# Buffer_1_2.net
KiCad netlist of a schematic drawn in EAGLE
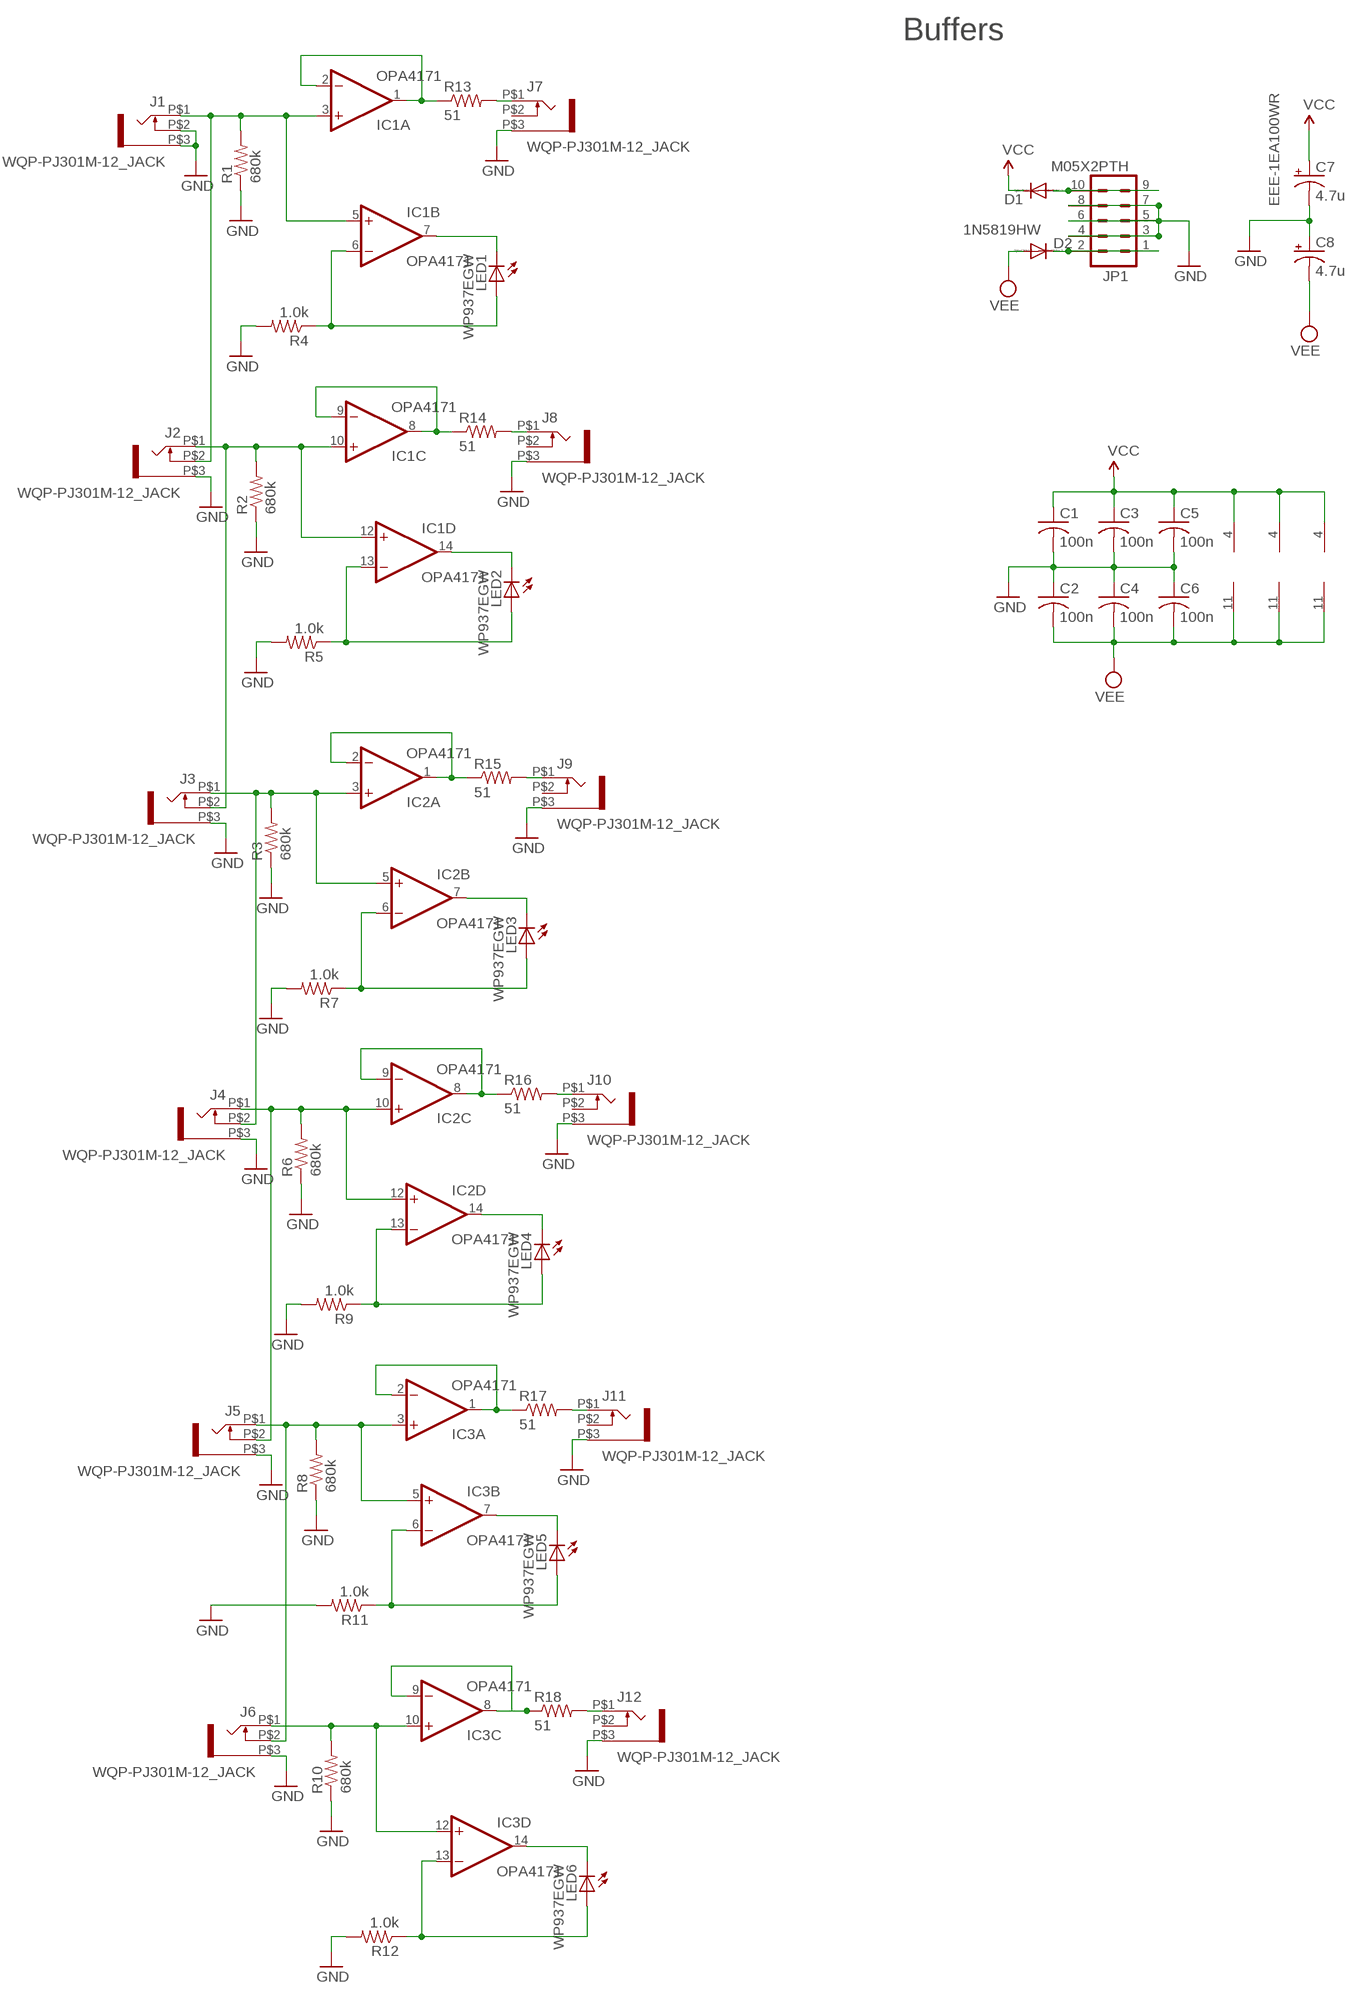
[diagram p0: schematic, sheet 1]

(export (version "E")
  (design (tool "Eeschema 10.0.6"))
  (components
    (comp (ref "C1")
      (value "100n")
      (footprint "eagle-import:C0603")
      (libsource (lib "eagle-import") (part "C-USC0603"))
    )
    (comp (ref "C2")
      (value "100n")
      (footprint "eagle-import:C0603")
      (libsource (lib "eagle-import") (part "C-USC0603"))
    )
    (comp (ref "C3")
      (value "100n")
      (footprint "eagle-import:C0603")
      (libsource (lib "eagle-import") (part "C-USC0603"))
    )
    (comp (ref "C4")
      (value "100n")
      (footprint "eagle-import:C0603")
      (libsource (lib "eagle-import") (part "C-USC0603"))
    )
    (comp (ref "C5")
      (value "100n")
      (footprint "eagle-import:C0603")
      (libsource (lib "eagle-import") (part "C-USC0603"))
    )
    (comp (ref "C6")
      (value "100n")
      (footprint "eagle-import:C0603")
      (libsource (lib "eagle-import") (part "C-USC0603"))
    )
    (comp (ref "C7")
      (value "4.7u")
      (footprint "eagle-import:PANASONIC_A")
      (libsource (lib "eagle-import") (part "CPOL-USA"))
    )
    (comp (ref "C8")
      (value "4.7u")
      (footprint "eagle-import:PANASONIC_A")
      (libsource (lib "eagle-import") (part "CPOL-USA"))
    )
    (comp (ref "D1")
      (value "1N5819HW")
      (footprint "eagle-import:SOD123")
      (libsource (lib "eagle-import") (part "DIODE-SOD123"))
    )
    (comp (ref "D2")
      (value "1N5819HW")
      (footprint "eagle-import:SOD123")
      (libsource (lib "eagle-import") (part "DIODE-SOD123"))
    )
    (comp (ref "IC1")
      (value "OPA4171")
      (footprint "eagle-import:TSSOP14")
      (libsource (lib "eagle-import") (part "TL074PW"))
    )
    (comp (ref "IC2")
      (value "OPA4171")
      (footprint "eagle-import:TSSOP14")
      (libsource (lib "eagle-import") (part "TL074PW"))
    )
    (comp (ref "IC3")
      (value "OPA4171")
      (footprint "eagle-import:TSSOP14")
      (libsource (lib "eagle-import") (part "TL074PW"))
    )
    (comp (ref "J1")
      (value "WQP-PJ301M-12_JACK")
      (footprint "eagle-import:WQP-PJ301M-12_JACK")
      (libsource (lib "eagle-import") (part "WQP-PJ301M-12_JACK"))
    )
    (comp (ref "J2")
      (value "WQP-PJ301M-12_JACK")
      (footprint "eagle-import:WQP-PJ301M-12_JACK")
      (libsource (lib "eagle-import") (part "WQP-PJ301M-12_JACK"))
    )
    (comp (ref "J3")
      (value "WQP-PJ301M-12_JACK")
      (footprint "eagle-import:WQP-PJ301M-12_JACK")
      (libsource (lib "eagle-import") (part "WQP-PJ301M-12_JACK"))
    )
    (comp (ref "J4")
      (value "WQP-PJ301M-12_JACK")
      (footprint "eagle-import:WQP-PJ301M-12_JACK")
      (libsource (lib "eagle-import") (part "WQP-PJ301M-12_JACK"))
    )
    (comp (ref "J5")
      (value "WQP-PJ301M-12_JACK")
      (footprint "eagle-import:WQP-PJ301M-12_JACK")
      (libsource (lib "eagle-import") (part "WQP-PJ301M-12_JACK"))
    )
    (comp (ref "J6")
      (value "WQP-PJ301M-12_JACK")
      (footprint "eagle-import:WQP-PJ301M-12_JACK")
      (libsource (lib "eagle-import") (part "WQP-PJ301M-12_JACK"))
    )
    (comp (ref "J7")
      (value "WQP-PJ301M-12_JACK")
      (footprint "eagle-import:WQP-PJ301M-12_JACK")
      (libsource (lib "eagle-import") (part "WQP-PJ301M-12_JACK"))
    )
    (comp (ref "J8")
      (value "WQP-PJ301M-12_JACK")
      (footprint "eagle-import:WQP-PJ301M-12_JACK")
      (libsource (lib "eagle-import") (part "WQP-PJ301M-12_JACK"))
    )
    (comp (ref "J9")
      (value "WQP-PJ301M-12_JACK")
      (footprint "eagle-import:WQP-PJ301M-12_JACK")
      (libsource (lib "eagle-import") (part "WQP-PJ301M-12_JACK"))
    )
    (comp (ref "J10")
      (value "WQP-PJ301M-12_JACK")
      (footprint "eagle-import:WQP-PJ301M-12_JACK")
      (libsource (lib "eagle-import") (part "WQP-PJ301M-12_JACK"))
    )
    (comp (ref "J11")
      (value "WQP-PJ301M-12_JACK")
      (footprint "eagle-import:WQP-PJ301M-12_JACK")
      (libsource (lib "eagle-import") (part "WQP-PJ301M-12_JACK"))
    )
    (comp (ref "J12")
      (value "WQP-PJ301M-12_JACK")
      (footprint "eagle-import:WQP-PJ301M-12_JACK")
      (libsource (lib "eagle-import") (part "WQP-PJ301M-12_JACK"))
    )
    (comp (ref "JP1")
      (value "M05X2PTH")
      (footprint "eagle-import:AVR_ICSP")
      (libsource (lib "eagle-import") (part "M05X2PTH"))
    )
    (comp (ref "LED1")
      (value "WP937EGW")
      (footprint "eagle-import:LED3MM")
      (libsource (lib "eagle-import") (part "LED3MM"))
    )
    (comp (ref "LED2")
      (value "WP937EGW")
      (footprint "eagle-import:LED3MM")
      (libsource (lib "eagle-import") (part "LED3MM"))
    )
    (comp (ref "LED3")
      (value "WP937EGW")
      (footprint "eagle-import:LED3MM")
      (libsource (lib "eagle-import") (part "LED3MM"))
    )
    (comp (ref "LED4")
      (value "WP937EGW")
      (footprint "eagle-import:LED3MM")
      (libsource (lib "eagle-import") (part "LED3MM"))
    )
    (comp (ref "LED5")
      (value "WP937EGW")
      (footprint "eagle-import:LED3MM")
      (libsource (lib "eagle-import") (part "LED3MM"))
    )
    (comp (ref "LED6")
      (value "WP937EGW")
      (footprint "eagle-import:LED3MM")
      (libsource (lib "eagle-import") (part "LED3MM"))
    )
    (comp (ref "R1")
      (value "680k")
      (footprint "eagle-import:R0603")
      (libsource (lib "eagle-import") (part "resistor_348_R-US_R0603"))
    )
    (comp (ref "R2")
      (value "680k")
      (footprint "eagle-import:R0603")
      (libsource (lib "eagle-import") (part "resistor_348_R-US_R0603"))
    )
    (comp (ref "R3")
      (value "680k")
      (footprint "eagle-import:R0603")
      (libsource (lib "eagle-import") (part "resistor_348_R-US_R0603"))
    )
    (comp (ref "R4")
      (value "1.0k")
      (footprint "eagle-import:R0603")
      (libsource (lib "eagle-import") (part "R-US_R0603"))
    )
    (comp (ref "R5")
      (value "1.0k")
      (footprint "eagle-import:R0603")
      (libsource (lib "eagle-import") (part "R-US_R0603"))
    )
    (comp (ref "R6")
      (value "680k")
      (footprint "eagle-import:R0603")
      (libsource (lib "eagle-import") (part "resistor_348_R-US_R0603"))
    )
    (comp (ref "R7")
      (value "1.0k")
      (footprint "eagle-import:R0603")
      (libsource (lib "eagle-import") (part "R-US_R0603"))
    )
    (comp (ref "R8")
      (value "680k")
      (footprint "eagle-import:R0603")
      (libsource (lib "eagle-import") (part "resistor_348_R-US_R0603"))
    )
    (comp (ref "R9")
      (value "1.0k")
      (footprint "eagle-import:R0603")
      (libsource (lib "eagle-import") (part "R-US_R0603"))
    )
    (comp (ref "R10")
      (value "680k")
      (footprint "eagle-import:R0603")
      (libsource (lib "eagle-import") (part "resistor_348_R-US_R0603"))
    )
    (comp (ref "R11")
      (value "1.0k")
      (footprint "eagle-import:R0603")
      (libsource (lib "eagle-import") (part "R-US_R0603"))
    )
    (comp (ref "R12")
      (value "1.0k")
      (footprint "eagle-import:R0603")
      (libsource (lib "eagle-import") (part "R-US_R0603"))
    )
    (comp (ref "R13")
      (value "51")
      (footprint "eagle-import:R0603")
      (libsource (lib "eagle-import") (part "resistor_348_R-US_R0603"))
    )
    (comp (ref "R14")
      (value "51")
      (footprint "eagle-import:R0603")
      (libsource (lib "eagle-import") (part "resistor_348_R-US_R0603"))
    )
    (comp (ref "R15")
      (value "51")
      (footprint "eagle-import:R0603")
      (libsource (lib "eagle-import") (part "resistor_348_R-US_R0603"))
    )
    (comp (ref "R16")
      (value "51")
      (footprint "eagle-import:R0603")
      (libsource (lib "eagle-import") (part "resistor_348_R-US_R0603"))
    )
    (comp (ref "R17")
      (value "51")
      (footprint "eagle-import:R0603")
      (libsource (lib "eagle-import") (part "resistor_348_R-US_R0603"))
    )
    (comp (ref "R18")
      (value "51")
      (footprint "eagle-import:R0603")
      (libsource (lib "eagle-import") (part "resistor_348_R-US_R0603"))
    )
  )
  (nets
    (net (code "1") (name "GND") (class "Default")
      (node (ref "C1") (pin "2") (pinfunction "2_2") (pintype "passive"))
      (node (ref "C2") (pin "1") (pinfunction "1_1") (pintype "passive"))
      (node (ref "C3") (pin "2") (pinfunction "2_2") (pintype "passive"))
      (node (ref "C4") (pin "1") (pinfunction "1_1") (pintype "passive"))
      (node (ref "C5") (pin "2") (pinfunction "2_2") (pintype "passive"))
      (node (ref "C6") (pin "1") (pinfunction "1_1") (pintype "passive"))
      (node (ref "C7") (pin "-") (pinfunction "-_-") (pintype "passive"))
      (node (ref "C8") (pin "+") (pinfunction "+_+") (pintype "passive"))
      (node (ref "J1") (pin "P$2") (pinfunction "3_P$2") (pintype "passive"))
      (node (ref "J1") (pin "P$3") (pinfunction "1_P$3") (pintype "passive"))
      (node (ref "J10") (pin "P$3") (pinfunction "1_P$3") (pintype "passive"))
      (node (ref "J11") (pin "P$3") (pinfunction "1_P$3") (pintype "passive"))
      (node (ref "J12") (pin "P$3") (pinfunction "1_P$3") (pintype "passive"))
      (node (ref "J2") (pin "P$3") (pinfunction "1_P$3") (pintype "passive"))
      (node (ref "J3") (pin "P$3") (pinfunction "1_P$3") (pintype "passive"))
      (node (ref "J4") (pin "P$3") (pinfunction "1_P$3") (pintype "passive"))
      (node (ref "J5") (pin "P$3") (pinfunction "1_P$3") (pintype "passive"))
      (node (ref "J6") (pin "P$3") (pinfunction "1_P$3") (pintype "passive"))
      (node (ref "J7") (pin "P$3") (pinfunction "1_P$3") (pintype "passive"))
      (node (ref "J8") (pin "P$3") (pinfunction "1_P$3") (pintype "passive"))
      (node (ref "J9") (pin "P$3") (pinfunction "1_P$3") (pintype "passive"))
      (node (ref "JP1") (pin "3") (pinfunction "3_3") (pintype "passive"))
      (node (ref "JP1") (pin "4") (pinfunction "4_4") (pintype "passive"))
      (node (ref "JP1") (pin "5") (pinfunction "5_5") (pintype "passive"))
      (node (ref "JP1") (pin "6") (pinfunction "6_6") (pintype "passive"))
      (node (ref "JP1") (pin "7") (pinfunction "7_7") (pintype "passive"))
      (node (ref "JP1") (pin "8") (pinfunction "8_8") (pintype "passive"))
      (node (ref "R1") (pin "1") (pinfunction "1_1") (pintype "passive"))
      (node (ref "R10") (pin "1") (pinfunction "1_1") (pintype "passive"))
      (node (ref "R11") (pin "2") (pinfunction "2_2") (pintype "passive"))
      (node (ref "R12") (pin "2") (pinfunction "2_2") (pintype "passive"))
      (node (ref "R2") (pin "1") (pinfunction "1_1") (pintype "passive"))
      (node (ref "R3") (pin "1") (pinfunction "1_1") (pintype "passive"))
      (node (ref "R4") (pin "2") (pinfunction "2_2") (pintype "passive"))
      (node (ref "R5") (pin "2") (pinfunction "2_2") (pintype "passive"))
      (node (ref "R6") (pin "1") (pinfunction "1_1") (pintype "passive"))
      (node (ref "R7") (pin "2") (pinfunction "2_2") (pintype "passive"))
      (node (ref "R8") (pin "1") (pinfunction "1_1") (pintype "passive"))
      (node (ref "R9") (pin "2") (pinfunction "2_2") (pintype "passive"))
    )
    (net (code "2") (name "Net-(D1-PadA)") (class "Default")
      (node (ref "D1") (pin "A") (pinfunction "A_A") (pintype "passive"))
      (node (ref "JP1") (pin "10") (pinfunction "10_10") (pintype "passive"))
      (node (ref "JP1") (pin "9") (pinfunction "9_9") (pintype "passive"))
    )
    (net (code "3") (name "Net-(D2-PadC)") (class "Default")
      (node (ref "D2") (pin "C") (pinfunction "C_C") (pintype "passive"))
      (node (ref "JP1") (pin "1") (pinfunction "1_1") (pintype "passive"))
      (node (ref "JP1") (pin "2") (pinfunction "2_2") (pintype "passive"))
    )
    (net (code "4") (name "Net-(IC1A-+IN)") (class "Default")
      (node (ref "IC1") (pin "3") (pinfunction "+IN_3") (pintype "input"))
      (node (ref "IC1") (pin "5") (pinfunction "+IN_5") (pintype "input"))
      (node (ref "J1") (pin "P$1") (pinfunction "2_P$1") (pintype "passive"))
      (node (ref "J2") (pin "P$2") (pinfunction "3_P$2") (pintype "passive"))
      (node (ref "R1") (pin "2") (pinfunction "2_2") (pintype "passive"))
    )
    (net (code "5") (name "Net-(IC1A--IN)") (class "Default")
      (node (ref "IC1") (pin "1") (pinfunction "OUT_1") (pintype "output"))
      (node (ref "IC1") (pin "2") (pinfunction "-IN_2") (pintype "input"))
      (node (ref "R13") (pin "1") (pinfunction "1_1") (pintype "passive"))
    )
    (net (code "6") (name "Net-(IC1B--IN)") (class "Default")
      (node (ref "IC1") (pin "6") (pinfunction "-IN_6") (pintype "input"))
      (node (ref "LED1") (pin "A") (pinfunction "A_A") (pintype "passive"))
      (node (ref "R4") (pin "1") (pinfunction "1_1") (pintype "passive"))
    )
    (net (code "7") (name "Net-(IC1B-OUT)") (class "Default")
      (node (ref "IC1") (pin "7") (pinfunction "OUT_7") (pintype "output"))
      (node (ref "LED1") (pin "K") (pinfunction "C_K") (pintype "passive"))
    )
    (net (code "8") (name "Net-(IC1C-+IN)") (class "Default")
      (node (ref "IC1") (pin "10") (pinfunction "+IN_10") (pintype "input"))
      (node (ref "IC1") (pin "12") (pinfunction "+IN_12") (pintype "input"))
      (node (ref "J2") (pin "P$1") (pinfunction "2_P$1") (pintype "passive"))
      (node (ref "J3") (pin "P$2") (pinfunction "3_P$2") (pintype "passive"))
      (node (ref "R2") (pin "2") (pinfunction "2_2") (pintype "passive"))
    )
    (net (code "9") (name "Net-(IC1C--IN)") (class "Default")
      (node (ref "IC1") (pin "8") (pinfunction "OUT_8") (pintype "output"))
      (node (ref "IC1") (pin "9") (pinfunction "-IN_9") (pintype "input"))
      (node (ref "R14") (pin "1") (pinfunction "1_1") (pintype "passive"))
    )
    (net (code "10") (name "Net-(IC1D--IN)") (class "Default")
      (node (ref "IC1") (pin "13") (pinfunction "-IN_13") (pintype "input"))
      (node (ref "LED2") (pin "A") (pinfunction "A_A") (pintype "passive"))
      (node (ref "R5") (pin "1") (pinfunction "1_1") (pintype "passive"))
    )
    (net (code "11") (name "Net-(IC1D-OUT)") (class "Default")
      (node (ref "IC1") (pin "14") (pinfunction "OUT_14") (pintype "output"))
      (node (ref "LED2") (pin "K") (pinfunction "C_K") (pintype "passive"))
    )
    (net (code "12") (name "Net-(IC2A-+IN)") (class "Default")
      (node (ref "IC2") (pin "3") (pinfunction "+IN_3") (pintype "input"))
      (node (ref "IC2") (pin "5") (pinfunction "+IN_5") (pintype "input"))
      (node (ref "J3") (pin "P$1") (pinfunction "2_P$1") (pintype "passive"))
      (node (ref "J4") (pin "P$2") (pinfunction "3_P$2") (pintype "passive"))
      (node (ref "R3") (pin "2") (pinfunction "2_2") (pintype "passive"))
    )
    (net (code "13") (name "Net-(IC2A--IN)") (class "Default")
      (node (ref "IC2") (pin "1") (pinfunction "OUT_1") (pintype "output"))
      (node (ref "IC2") (pin "2") (pinfunction "-IN_2") (pintype "input"))
      (node (ref "R15") (pin "1") (pinfunction "1_1") (pintype "passive"))
    )
    (net (code "14") (name "Net-(IC2B--IN)") (class "Default")
      (node (ref "IC2") (pin "6") (pinfunction "-IN_6") (pintype "input"))
      (node (ref "LED3") (pin "A") (pinfunction "A_A") (pintype "passive"))
      (node (ref "R7") (pin "1") (pinfunction "1_1") (pintype "passive"))
    )
    (net (code "15") (name "Net-(IC2B-OUT)") (class "Default")
      (node (ref "IC2") (pin "7") (pinfunction "OUT_7") (pintype "output"))
      (node (ref "LED3") (pin "K") (pinfunction "C_K") (pintype "passive"))
    )
    (net (code "16") (name "Net-(IC2C-+IN)") (class "Default")
      (node (ref "IC2") (pin "10") (pinfunction "+IN_10") (pintype "input"))
      (node (ref "IC2") (pin "12") (pinfunction "+IN_12") (pintype "input"))
      (node (ref "J4") (pin "P$1") (pinfunction "2_P$1") (pintype "passive"))
      (node (ref "J5") (pin "P$2") (pinfunction "3_P$2") (pintype "passive"))
      (node (ref "R6") (pin "2") (pinfunction "2_2") (pintype "passive"))
    )
    (net (code "17") (name "Net-(IC2C--IN)") (class "Default")
      (node (ref "IC2") (pin "8") (pinfunction "OUT_8") (pintype "output"))
      (node (ref "IC2") (pin "9") (pinfunction "-IN_9") (pintype "input"))
      (node (ref "R16") (pin "1") (pinfunction "1_1") (pintype "passive"))
    )
    (net (code "18") (name "Net-(IC2D--IN)") (class "Default")
      (node (ref "IC2") (pin "13") (pinfunction "-IN_13") (pintype "input"))
      (node (ref "LED4") (pin "A") (pinfunction "A_A") (pintype "passive"))
      (node (ref "R9") (pin "1") (pinfunction "1_1") (pintype "passive"))
    )
    (net (code "19") (name "Net-(IC2D-OUT)") (class "Default")
      (node (ref "IC2") (pin "14") (pinfunction "OUT_14") (pintype "output"))
      (node (ref "LED4") (pin "K") (pinfunction "C_K") (pintype "passive"))
    )
    (net (code "20") (name "Net-(IC3A-+IN)") (class "Default")
      (node (ref "IC3") (pin "3") (pinfunction "+IN_3") (pintype "input"))
      (node (ref "IC3") (pin "5") (pinfunction "+IN_5") (pintype "input"))
      (node (ref "J5") (pin "P$1") (pinfunction "2_P$1") (pintype "passive"))
      (node (ref "J6") (pin "P$2") (pinfunction "3_P$2") (pintype "passive"))
      (node (ref "R8") (pin "2") (pinfunction "2_2") (pintype "passive"))
    )
    (net (code "21") (name "Net-(IC3A--IN)") (class "Default")
      (node (ref "IC3") (pin "1") (pinfunction "OUT_1") (pintype "output"))
      (node (ref "IC3") (pin "2") (pinfunction "-IN_2") (pintype "input"))
      (node (ref "R17") (pin "1") (pinfunction "1_1") (pintype "passive"))
    )
    (net (code "22") (name "Net-(IC3B--IN)") (class "Default")
      (node (ref "IC3") (pin "6") (pinfunction "-IN_6") (pintype "input"))
      (node (ref "LED5") (pin "A") (pinfunction "A_A") (pintype "passive"))
      (node (ref "R11") (pin "1") (pinfunction "1_1") (pintype "passive"))
    )
    (net (code "23") (name "Net-(IC3B-OUT)") (class "Default")
      (node (ref "IC3") (pin "7") (pinfunction "OUT_7") (pintype "output"))
      (node (ref "LED5") (pin "K") (pinfunction "C_K") (pintype "passive"))
    )
    (net (code "24") (name "Net-(IC3C-+IN)") (class "Default")
      (node (ref "IC3") (pin "10") (pinfunction "+IN_10") (pintype "input"))
      (node (ref "IC3") (pin "12") (pinfunction "+IN_12") (pintype "input"))
      (node (ref "J6") (pin "P$1") (pinfunction "2_P$1") (pintype "passive"))
      (node (ref "R10") (pin "2") (pinfunction "2_2") (pintype "passive"))
    )
    (net (code "25") (name "Net-(IC3C--IN)") (class "Default")
      (node (ref "IC3") (pin "8") (pinfunction "OUT_8") (pintype "output"))
      (node (ref "IC3") (pin "9") (pinfunction "-IN_9") (pintype "input"))
      (node (ref "R18") (pin "1") (pinfunction "1_1") (pintype "passive"))
    )
    (net (code "26") (name "Net-(IC3D--IN)") (class "Default")
      (node (ref "IC3") (pin "13") (pinfunction "-IN_13") (pintype "input"))
      (node (ref "LED6") (pin "A") (pinfunction "A_A") (pintype "passive"))
      (node (ref "R12") (pin "1") (pinfunction "1_1") (pintype "passive"))
    )
    (net (code "27") (name "Net-(IC3D-OUT)") (class "Default")
      (node (ref "IC3") (pin "14") (pinfunction "OUT_14") (pintype "output"))
      (node (ref "LED6") (pin "K") (pinfunction "C_K") (pintype "passive"))
    )
    (net (code "28") (name "Net-(J7-2)") (class "Default")
      (node (ref "J7") (pin "P$1") (pinfunction "2_P$1") (pintype "passive"))
      (node (ref "R13") (pin "2") (pinfunction "2_2") (pintype "passive"))
    )
    (net (code "29") (name "Net-(J8-2)") (class "Default")
      (node (ref "J8") (pin "P$1") (pinfunction "2_P$1") (pintype "passive"))
      (node (ref "R14") (pin "2") (pinfunction "2_2") (pintype "passive"))
    )
    (net (code "30") (name "Net-(J9-2)") (class "Default")
      (node (ref "J9") (pin "P$1") (pinfunction "2_P$1") (pintype "passive"))
      (node (ref "R15") (pin "2") (pinfunction "2_2") (pintype "passive"))
    )
    (net (code "31") (name "Net-(J10-2)") (class "Default")
      (node (ref "J10") (pin "P$1") (pinfunction "2_P$1") (pintype "passive"))
      (node (ref "R16") (pin "2") (pinfunction "2_2") (pintype "passive"))
    )
    (net (code "32") (name "Net-(J11-2)") (class "Default")
      (node (ref "J11") (pin "P$1") (pinfunction "2_P$1") (pintype "passive"))
      (node (ref "R17") (pin "2") (pinfunction "2_2") (pintype "passive"))
    )
    (net (code "33") (name "Net-(J12-2)") (class "Default")
      (node (ref "J12") (pin "P$1") (pinfunction "2_P$1") (pintype "passive"))
      (node (ref "R18") (pin "2") (pinfunction "2_2") (pintype "passive"))
    )
    (net (code "34") (name "VCC") (class "Default")
      (node (ref "C1") (pin "1") (pinfunction "1_1") (pintype "passive"))
      (node (ref "C3") (pin "1") (pinfunction "1_1") (pintype "passive"))
      (node (ref "C5") (pin "1") (pinfunction "1_1") (pintype "passive"))
      (node (ref "C7") (pin "+") (pinfunction "+_+") (pintype "passive"))
      (node (ref "D1") (pin "C") (pinfunction "C_C") (pintype "passive"))
      (node (ref "IC1") (pin "4") (pinfunction "V+_4") (pintype "power_in"))
      (node (ref "IC2") (pin "4") (pinfunction "V+_4") (pintype "power_in"))
      (node (ref "IC3") (pin "4") (pinfunction "V+_4") (pintype "power_in"))
    )
    (net (code "35") (name "VEE") (class "Default")
      (node (ref "C2") (pin "2") (pinfunction "2_2") (pintype "passive"))
      (node (ref "C4") (pin "2") (pinfunction "2_2") (pintype "passive"))
      (node (ref "C6") (pin "2") (pinfunction "2_2") (pintype "passive"))
      (node (ref "C8") (pin "-") (pinfunction "-_-") (pintype "passive"))
      (node (ref "D2") (pin "A") (pinfunction "A_A") (pintype "passive"))
      (node (ref "IC1") (pin "11") (pinfunction "V-_11") (pintype "power_in"))
      (node (ref "IC2") (pin "11") (pinfunction "V-_11") (pintype "power_in"))
      (node (ref "IC3") (pin "11") (pinfunction "V-_11") (pintype "power_in"))
    )
    (net (code "36") (name "unconnected-(J7-3-PadP$2)") (class "Default")
      (node (ref "J7") (pin "P$2") (pinfunction "3_P$2") (pintype "passive"))
    )
    (net (code "37") (name "unconnected-(J8-3-PadP$2)") (class "Default")
      (node (ref "J8") (pin "P$2") (pinfunction "3_P$2") (pintype "passive"))
    )
    (net (code "38") (name "unconnected-(J9-3-PadP$2)") (class "Default")
      (node (ref "J9") (pin "P$2") (pinfunction "3_P$2") (pintype "passive"))
    )
    (net (code "39") (name "unconnected-(J10-3-PadP$2)") (class "Default")
      (node (ref "J10") (pin "P$2") (pinfunction "3_P$2") (pintype "passive"))
    )
    (net (code "40") (name "unconnected-(J11-3-PadP$2)") (class "Default")
      (node (ref "J11") (pin "P$2") (pinfunction "3_P$2") (pintype "passive"))
    )
    (net (code "41") (name "unconnected-(J12-3-PadP$2)") (class "Default")
      (node (ref "J12") (pin "P$2") (pinfunction "3_P$2") (pintype "passive"))
    )
  )
)
